# CAN2.net
KiCad netlist of a schematic drawn in Altium Designer
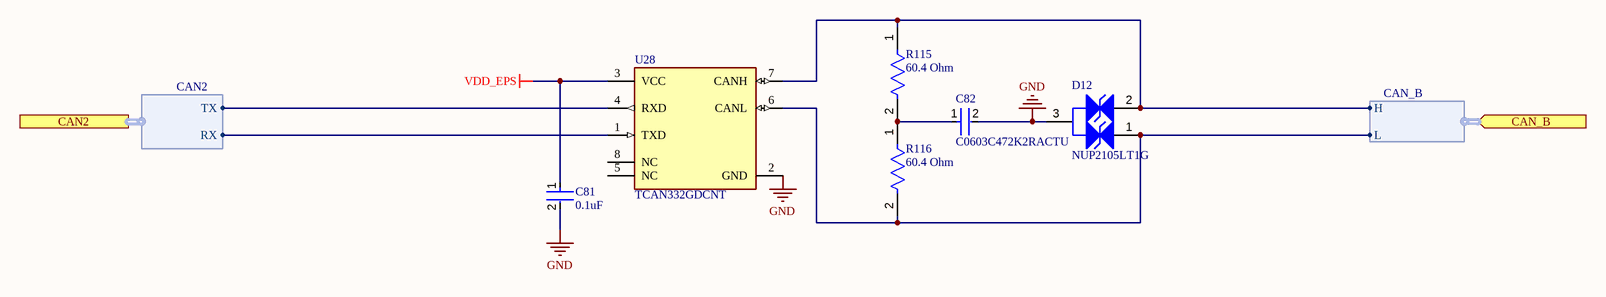
[diagram p0: CAN2.SchDoc]

(export (version "E")
  (design (tool "Eeschema 10.0.6"))
  (components
    (comp (ref "C81")
      (value "0.1uF")
      (footprint "FP-C0603C-CF-MFG")
      (description "CAP CER 0.1UF 50V X7R 0603")
      (fields (field (name "TOLERANCE") "0.1") (field (name "MANUFACTURER") "KEMET"))
      (libsource (lib "Altium Content Vault") (part "b4654b650e69147ec39a6b967a45e02"))
    )
    (comp (ref "C82")
      (value "C0603C472K2RACTU")
      (footprint "FP-C0603C-CF-MFG")
      (description "CAP CER 4700PF 200V 10% X7R 0603")
      (fields
        (field (name "OCTOPART") "https://octopart.com/c0603c472k2ractu-kemet-17058096")
        (field (name "MANUFACTURER") "KEMET")
      )
      (libsource (lib "Altium Content Vault") (part "b4654b650e69147ec39a6b967a45e02"))
    )
    (comp (ref "D12")
      (value "NUP2105LT1G")
      (footprint "ONSC-SOT-23-3-318-08_V")
      (description "Dual Line CAN Bus Protector, 3-Pin SOT-23, Pb-Free, Tape and Reel")
      (fields (field (name "MANUFACTURER") "On Semiconductor"))
      (libsource (lib "Altium Content Vault") (part "ONSC-NUP21X5X-SOT-23-3-318-08"))
    )
    (comp (ref "R115")
      (value "60.4 Ohm")
      (footprint "FP-RC1608-IPC_C")
      (description "Res Thick Film 0603 60.4Ω 1% 0.1W ±100ppm/°C Molded SMD T/R")
      (fields (field (name "TOLERANCE") "1%"))
      (libsource (lib "Altium Content Vault") (part "1029c3af85768c4190bb7ad29bc67b5"))
    )
    (comp (ref "R116")
      (value "60.4 Ohm")
      (footprint "FP-RC1608-IPC_C")
      (description "Res Thick Film 0603 60.4Ω 1% 0.1W ±100ppm/°C Molded SMD T/R")
      (fields (field (name "TOLERANCE") "1%"))
      (libsource (lib "Altium Content Vault") (part "1029c3af85768c4190bb7ad29bc67b5"))
    )
    (comp (ref "U28")
      (value "TCAN332GDCNT")
      (footprint "FP-DCN0008A-IPC_C")
      (description "IC TRANSCEIVER 1/1 SOT23-8")
      (libsource (lib "Altium Content Vault") (part "f57d81afad401941ce556981ca48666"))
    )
  )
  (nets
    (net (code "3") (name "/H") (class "Default")
      (node (ref "D12") (pin "2") (pinfunction "K_2") (pintype "passive"))
      (node (ref "R115") (pin "1") (pinfunction "1_1") (pintype "passive"))
      (node (ref "U28") (pin "7") (pinfunction "CANH_7") (pintype "bidirectional"))
    )
    (net (code "4") (name "/L") (class "Default")
      (node (ref "D12") (pin "1") (pinfunction "K_1") (pintype "passive"))
      (node (ref "R116") (pin "2") (pinfunction "2_2") (pintype "passive"))
      (node (ref "U28") (pin "6") (pinfunction "CANL_6") (pintype "bidirectional"))
    )
    (net (code "5") (name "/RX") (class "Default")
      (node (ref "U28") (pin "1") (pinfunction "TXD_1") (pintype "input"))
    )
    (net (code "6") (name "/TX") (class "Default")
      (node (ref "U28") (pin "4") (pinfunction "RXD_4") (pintype "output"))
    )
    (net (code "9") (name "GND") (class "Default")
      (node (ref "C81") (pin "2") (pinfunction "2_2") (pintype "passive"))
      (node (ref "C82") (pin "2") (pinfunction "2_2") (pintype "passive"))
      (node (ref "D12") (pin "3") (pinfunction "K_3") (pintype "passive"))
      (node (ref "U28") (pin "2") (pinfunction "GND_2") (pintype "power_in"))
    )
    (net (code "10") (name "Net-(C82-Pad1)") (class "Default")
      (node (ref "C82") (pin "1") (pinfunction "1_1") (pintype "passive"))
      (node (ref "R115") (pin "2") (pinfunction "2_2") (pintype "passive"))
      (node (ref "R116") (pin "1") (pinfunction "1_1") (pintype "passive"))
    )
    (net (code "11") (name "VDD_EPS") (class "Default")
      (node (ref "C81") (pin "1") (pinfunction "1_1") (pintype "passive"))
      (node (ref "U28") (pin "3") (pinfunction "VCC_3") (pintype "power_in"))
    )
    (net (code "12") (name "unconnected-(U28-NC-Pad5)") (class "Default")
      (node (ref "U28") (pin "5") (pinfunction "NC_5") (pintype "passive"))
    )
    (net (code "13") (name "unconnected-(U28-NC-Pad8)") (class "Default")
      (node (ref "U28") (pin "8") (pinfunction "NC_8") (pintype "passive"))
    )
  )
)
